# DRONE_ESP_SHIELD.net
KiCad netlist of a schematic drawn in EasyEDA
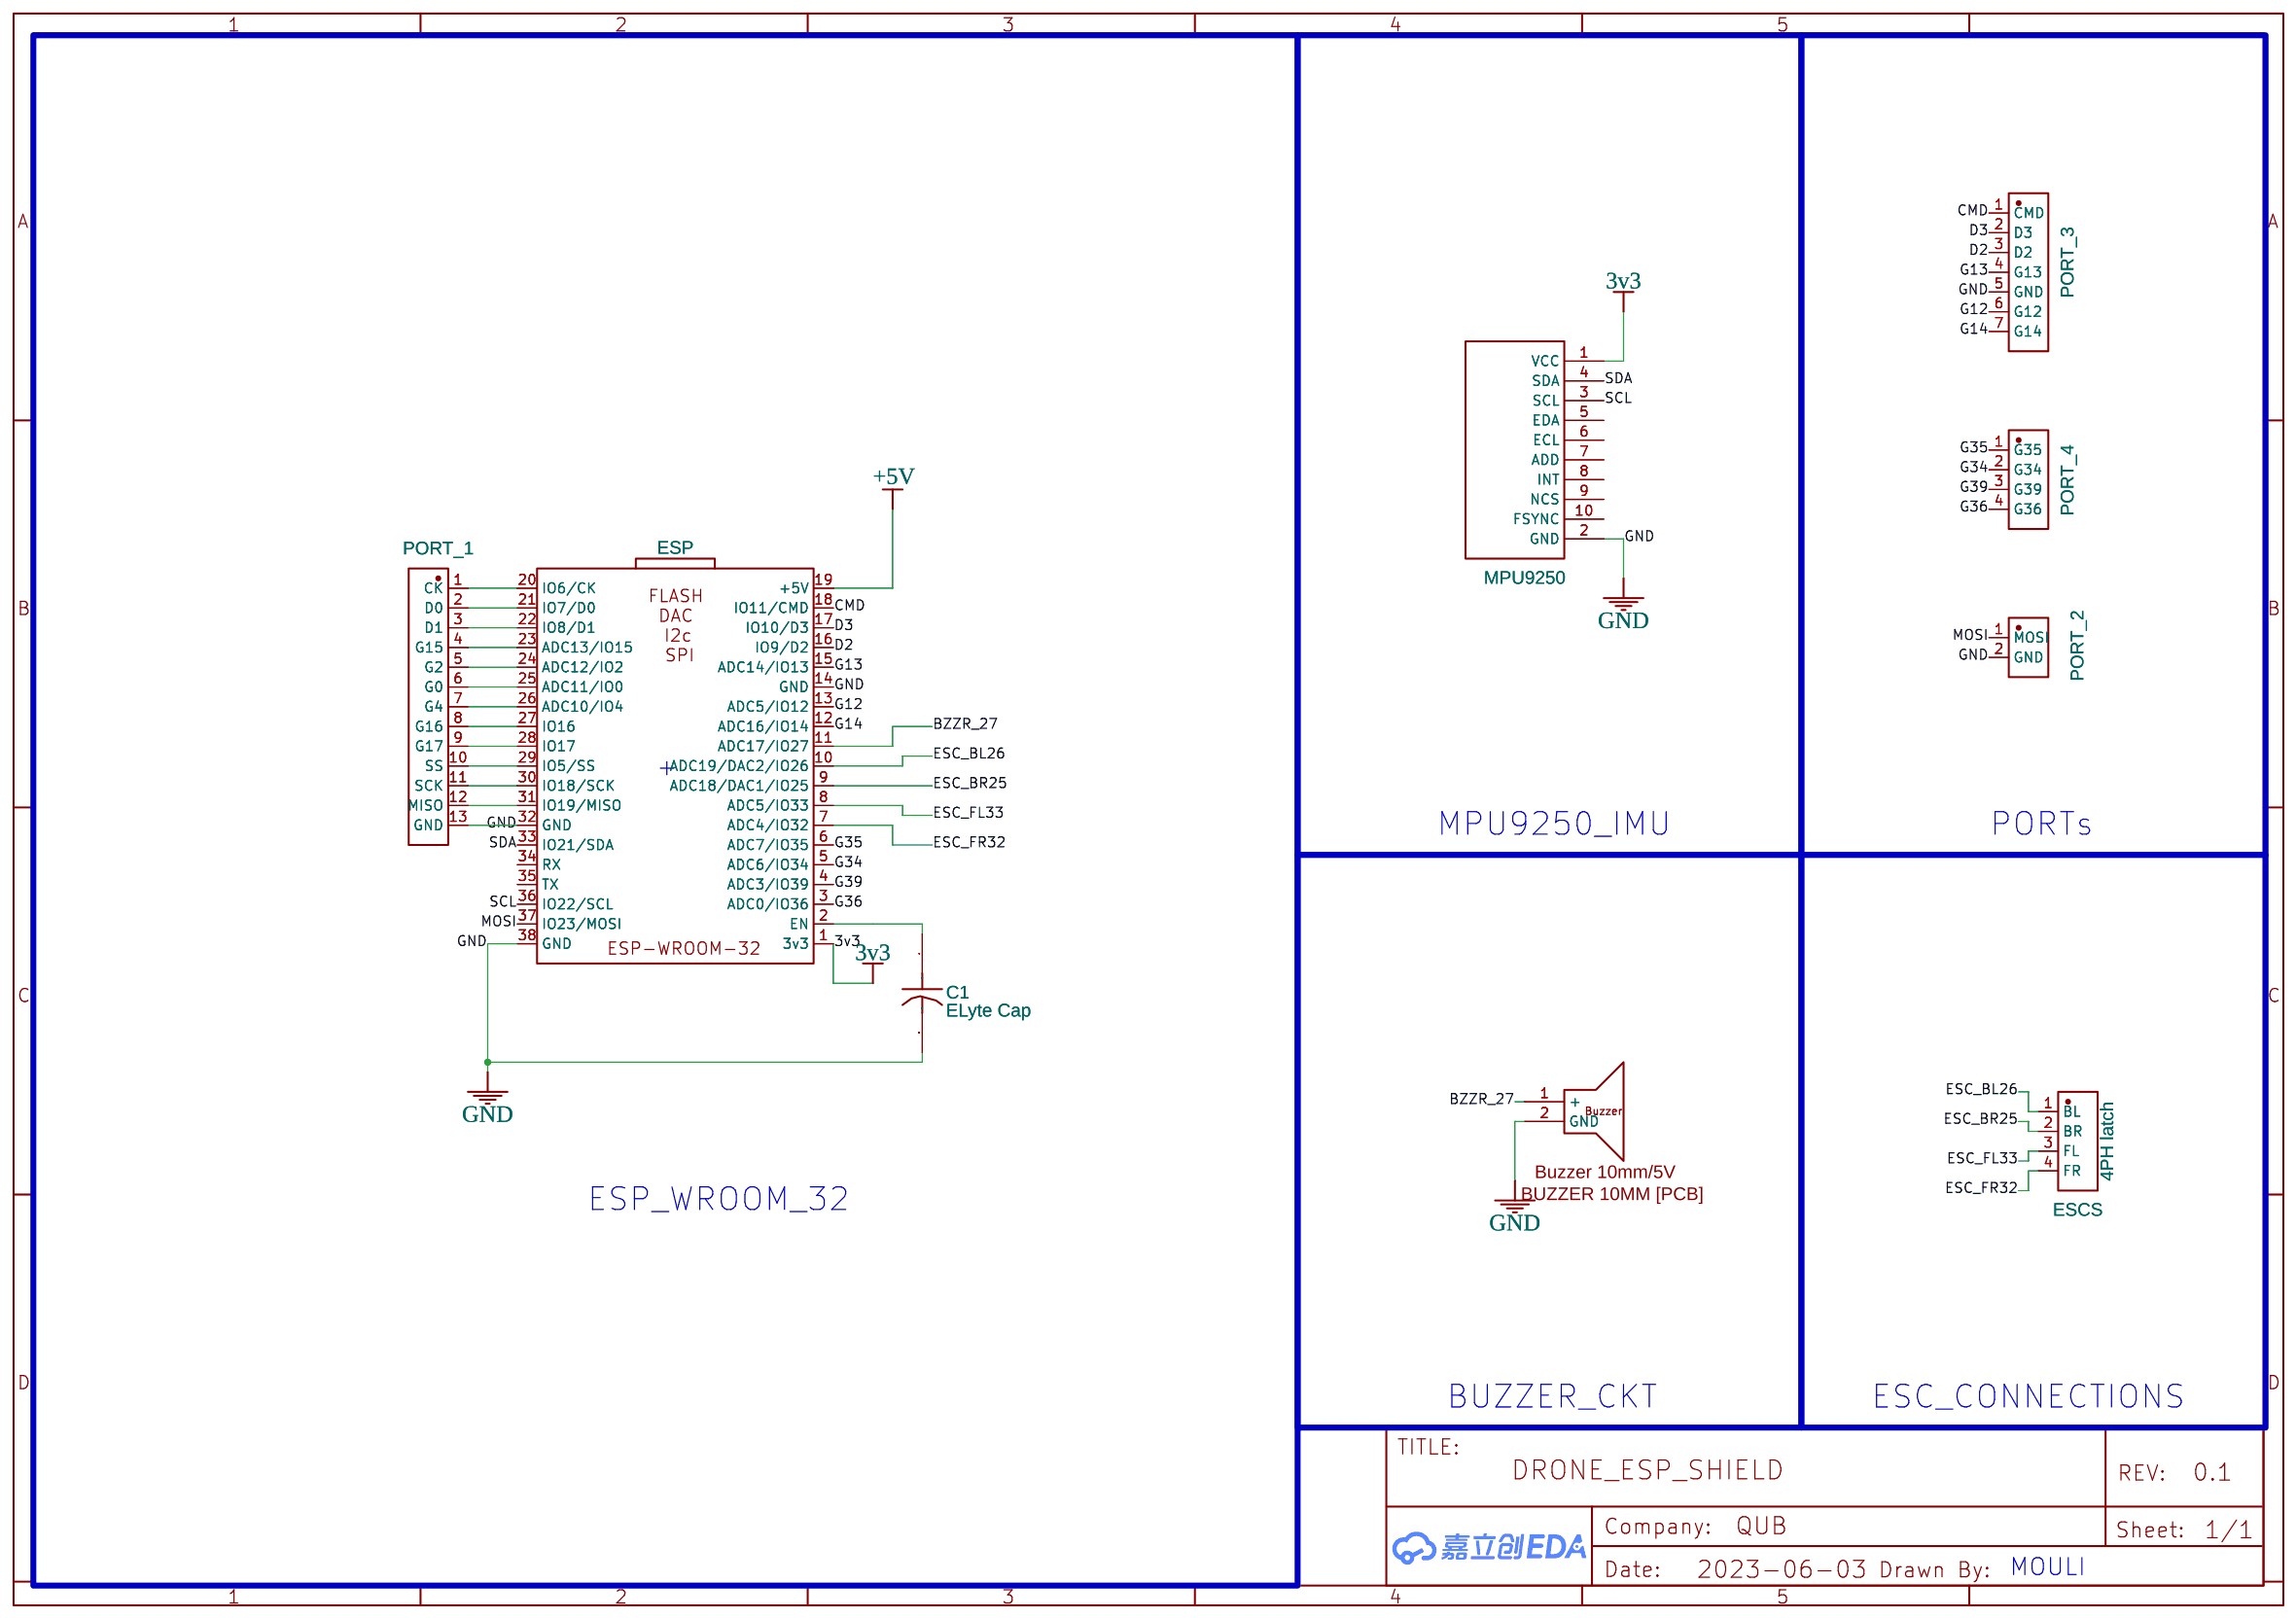
[diagram p0: schematic sheet]

(export (version "E")
  (design (tool "Eeschema 10.0.6"))
  (components
    (comp (ref "BUZZER")
      (value "Buzzer 10mm/5V")
      (fields (field (name "BOM_Manufacturer Part") "BUZZER"))
      (libsource (lib "") (part "Buzzer 10mm/5V"))
    )
    (comp (ref "C1") (value "ELyte Cap") (libsource (lib "") (part "Electrolitic Capacitor")))
    (comp (ref "ESCS")
      (value "4PH latch")
      (fields
        (field (name "BOM_Manufacturer Part") "A2541HWV-4P")
        (field (name "BOM_Supplier Part") "C5176037")
      )
      (libsource (lib "") (part "A2541HWV-4P_C5176037"))
    )
    (comp (ref "ESP")
      (value "ESP-WROOM-32D 38 Pins")
      (fields (field (name "BOM_Manufacturer Part") "ESP-WROOM-32"))
      (libsource (lib "") (part "ESP-WROOM-32D 38 Pins"))
    )
    (comp (ref "MPU9250") (value "MPU9250") (libsource (lib "") (part "MPU9250 MODULE")))
    (comp (ref "PORT_1")
      (value "EXT_PORT")
      (fields
        (field (name "BOM_Manufacturer Part") "PZ254-1-13-Z-8.5KK")
        (field (name "BOM_Supplier Part") "C3012215")
      )
      (libsource (lib "") (part "PZ254-1-13-Z-8.5KK"))
    )
    (comp (ref "PORT_2")
      (value "HDR102")
      (fields (field (name "BOM_Supplier Part") "C9900001420"))
      (libsource (lib "") (part "HDR102"))
    )
    (comp (ref "PORT_3")
      (value "PZ254-1-07-Z-C")
      (fields (field (name "BOM_Supplier Part") "C5156434"))
      (libsource (lib "") (part "PZ254-1-07-Z-C"))
    )
    (comp (ref "PORT_4")
      (value "0022285044")
      (fields (field (name "BOM_Supplier Part") "C9900016049"))
      (libsource (lib "") (part "0022285044"))
    )
  )
  (nets
    (net (code "1") (name "+5V") (class "Default")
      (node (ref "ESP") (pin "19") (pinfunction "+5V_19") (pintype "unspecified"))
    )
    (net (code "2") (name "/BZZR_27") (class "Default")
      (node (ref "BUZZER") (pin "1") (pinfunction "+_1") (pintype "unspecified"))
      (node (ref "ESP") (pin "11") (pinfunction "ADC17/IO27_11") (pintype "unspecified"))
    )
    (net (code "3") (name "/CMD") (class "Default")
      (node (ref "ESP") (pin "18") (pinfunction "IO11/CMD_18") (pintype "unspecified"))
      (node (ref "PORT_3") (pin "1") (pinfunction "CMD_1") (pintype "unspecified"))
    )
    (net (code "4") (name "/D2") (class "Default")
      (node (ref "ESP") (pin "16") (pinfunction "IO9/D2_16") (pintype "unspecified"))
      (node (ref "PORT_3") (pin "3") (pinfunction "D2_3") (pintype "unspecified"))
    )
    (net (code "5") (name "/D3") (class "Default")
      (node (ref "ESP") (pin "17") (pinfunction "IO10/D3_17") (pintype "unspecified"))
      (node (ref "PORT_3") (pin "2") (pinfunction "D3_2") (pintype "unspecified"))
    )
    (net (code "6") (name "/ESC_BL26") (class "Default")
      (node (ref "ESCS") (pin "1") (pinfunction "BL_1") (pintype "unspecified"))
      (node (ref "ESP") (pin "10") (pinfunction "ADC19/DAC2/IO26_10") (pintype "unspecified"))
    )
    (net (code "7") (name "/ESC_BR25") (class "Default")
      (node (ref "ESCS") (pin "2") (pinfunction "BR_2") (pintype "unspecified"))
      (node (ref "ESP") (pin "9") (pinfunction "ADC18/DAC1/IO25_9") (pintype "unspecified"))
    )
    (net (code "8") (name "/ESC_FL33") (class "Default")
      (node (ref "ESCS") (pin "3") (pinfunction "FL_3") (pintype "unspecified"))
      (node (ref "ESP") (pin "8") (pinfunction "ADC5/IO33_8") (pintype "unspecified"))
    )
    (net (code "9") (name "/ESC_FR32") (class "Default")
      (node (ref "ESCS") (pin "4") (pinfunction "FR_4") (pintype "unspecified"))
      (node (ref "ESP") (pin "7") (pinfunction "ADC4/IO32_7") (pintype "unspecified"))
    )
    (net (code "10") (name "/G12") (class "Default")
      (node (ref "ESP") (pin "13") (pinfunction "ADC5/IO12_13") (pintype "unspecified"))
      (node (ref "PORT_3") (pin "6") (pinfunction "G12_6") (pintype "unspecified"))
    )
    (net (code "11") (name "/G13") (class "Default")
      (node (ref "ESP") (pin "15") (pinfunction "ADC14/IO13_15") (pintype "unspecified"))
      (node (ref "PORT_3") (pin "4") (pinfunction "G13_4") (pintype "unspecified"))
    )
    (net (code "12") (name "/G14") (class "Default")
      (node (ref "ESP") (pin "12") (pinfunction "ADC16/IO14_12") (pintype "unspecified"))
      (node (ref "PORT_3") (pin "7") (pinfunction "G14_7") (pintype "unspecified"))
    )
    (net (code "13") (name "/G34") (class "Default")
      (node (ref "ESP") (pin "5") (pinfunction "ADC6/IO34_5") (pintype "unspecified"))
      (node (ref "PORT_4") (pin "2") (pinfunction "G34_2") (pintype "unspecified"))
    )
    (net (code "14") (name "/G35") (class "Default")
      (node (ref "ESP") (pin "6") (pinfunction "ADC7/IO35_6") (pintype "unspecified"))
      (node (ref "PORT_4") (pin "1") (pinfunction "G35_1") (pintype "unspecified"))
    )
    (net (code "15") (name "/G36") (class "Default")
      (node (ref "ESP") (pin "3") (pinfunction "ADC0/IO36_3") (pintype "unspecified"))
      (node (ref "PORT_4") (pin "4") (pinfunction "G36_4") (pintype "unspecified"))
    )
    (net (code "16") (name "/G39") (class "Default")
      (node (ref "ESP") (pin "4") (pinfunction "ADC3/IO39_4") (pintype "unspecified"))
      (node (ref "PORT_4") (pin "3") (pinfunction "G39_3") (pintype "unspecified"))
    )
    (net (code "17") (name "/MOSI") (class "Default")
      (node (ref "ESP") (pin "37") (pinfunction "IO23/MOSI_37") (pintype "unspecified"))
      (node (ref "PORT_2") (pin "1") (pinfunction "MOSI_1") (pintype "unspecified"))
    )
    (net (code "18") (name "/SCL") (class "Default")
      (node (ref "ESP") (pin "36") (pinfunction "IO22/SCL_36") (pintype "unspecified"))
      (node (ref "MPU9250") (pin "3") (pinfunction "SCL_3") (pintype "bidirectional"))
    )
    (net (code "19") (name "/SDA") (class "Default")
      (node (ref "ESP") (pin "33") (pinfunction "IO21/SDA_33") (pintype "unspecified"))
      (node (ref "MPU9250") (pin "4") (pinfunction "SDA_4") (pintype "bidirectional"))
    )
    (net (code "20") (name "3v3") (class "Default")
      (node (ref "ESP") (pin "1") (pinfunction "3v3_1") (pintype "unspecified"))
      (node (ref "MPU9250") (pin "1") (pinfunction "VCC_1") (pintype "passive"))
    )
    (net (code "21") (name "GND") (class "Default")
      (node (ref "BUZZER") (pin "2") (pinfunction "GND_2") (pintype "unspecified"))
      (node (ref "C1") (pin "2") (pinfunction "2_2") (pintype "unspecified"))
      (node (ref "ESP") (pin "14") (pinfunction "GND_14") (pintype "unspecified"))
      (node (ref "ESP") (pin "32") (pinfunction "GND_32") (pintype "unspecified"))
      (node (ref "ESP") (pin "38") (pinfunction "GND_38") (pintype "unspecified"))
      (node (ref "MPU9250") (pin "2") (pinfunction "GND_2") (pintype "passive"))
      (node (ref "PORT_1") (pin "13") (pinfunction "GND_13") (pintype "unspecified"))
      (node (ref "PORT_2") (pin "2") (pinfunction "GND_2") (pintype "unspecified"))
      (node (ref "PORT_3") (pin "5") (pinfunction "GND_5") (pintype "unspecified"))
    )
    (net (code "22") (name "Net-(ESP-ADC10{slash}IO4)") (class "Default")
      (node (ref "ESP") (pin "26") (pinfunction "ADC10/IO4_26") (pintype "unspecified"))
      (node (ref "PORT_1") (pin "7") (pinfunction "G4_7") (pintype "unspecified"))
    )
    (net (code "23") (name "Net-(ESP-ADC11{slash}IO0)") (class "Default")
      (node (ref "ESP") (pin "25") (pinfunction "ADC11/IO0_25") (pintype "unspecified"))
      (node (ref "PORT_1") (pin "6") (pinfunction "G0_6") (pintype "unspecified"))
    )
    (net (code "24") (name "Net-(ESP-ADC12{slash}IO2)") (class "Default")
      (node (ref "ESP") (pin "24") (pinfunction "ADC12/IO2_24") (pintype "unspecified"))
      (node (ref "PORT_1") (pin "5") (pinfunction "G2_5") (pintype "unspecified"))
    )
    (net (code "25") (name "Net-(ESP-ADC13{slash}IO15)") (class "Default")
      (node (ref "ESP") (pin "23") (pinfunction "ADC13/IO15_23") (pintype "unspecified"))
      (node (ref "PORT_1") (pin "4") (pinfunction "G15_4") (pintype "unspecified"))
    )
    (net (code "26") (name "Net-(ESP-EN)") (class "Default")
      (node (ref "C1") (pin "1") (pinfunction "1_1") (pintype "unspecified"))
      (node (ref "ESP") (pin "2") (pinfunction "EN_2") (pintype "unspecified"))
    )
    (net (code "27") (name "Net-(ESP-IO5{slash}SS)") (class "Default")
      (node (ref "ESP") (pin "29") (pinfunction "IO5/SS_29") (pintype "unspecified"))
      (node (ref "PORT_1") (pin "10") (pinfunction "SS_10") (pintype "unspecified"))
    )
    (net (code "28") (name "Net-(ESP-IO6{slash}CK)") (class "Default")
      (node (ref "ESP") (pin "20") (pinfunction "IO6/CK_20") (pintype "unspecified"))
      (node (ref "PORT_1") (pin "1") (pinfunction "CK_1") (pintype "unspecified"))
    )
    (net (code "29") (name "Net-(ESP-IO7{slash}D0)") (class "Default")
      (node (ref "ESP") (pin "21") (pinfunction "IO7/D0_21") (pintype "unspecified"))
      (node (ref "PORT_1") (pin "2") (pinfunction "D0_2") (pintype "unspecified"))
    )
    (net (code "30") (name "Net-(ESP-IO8{slash}D1)") (class "Default")
      (node (ref "ESP") (pin "22") (pinfunction "IO8/D1_22") (pintype "unspecified"))
      (node (ref "PORT_1") (pin "3") (pinfunction "D1_3") (pintype "unspecified"))
    )
    (net (code "31") (name "Net-(ESP-IO16)") (class "Default")
      (node (ref "ESP") (pin "27") (pinfunction "IO16_27") (pintype "unspecified"))
      (node (ref "PORT_1") (pin "8") (pinfunction "G16_8") (pintype "unspecified"))
    )
    (net (code "32") (name "Net-(ESP-IO17)") (class "Default")
      (node (ref "ESP") (pin "28") (pinfunction "IO17_28") (pintype "unspecified"))
      (node (ref "PORT_1") (pin "9") (pinfunction "G17_9") (pintype "unspecified"))
    )
    (net (code "33") (name "Net-(ESP-IO18{slash}SCK)") (class "Default")
      (node (ref "ESP") (pin "30") (pinfunction "IO18/SCK_30") (pintype "unspecified"))
      (node (ref "PORT_1") (pin "11") (pinfunction "SCK_11") (pintype "unspecified"))
    )
    (net (code "34") (name "Net-(ESP-IO19{slash}MISO)") (class "Default")
      (node (ref "ESP") (pin "31") (pinfunction "IO19/MISO_31") (pintype "unspecified"))
      (node (ref "PORT_1") (pin "12") (pinfunction "MISO_12") (pintype "unspecified"))
    )
    (net (code "35") (name "unconnected-(ESP-RX-Pad34)") (class "Default")
      (node (ref "ESP") (pin "34") (pinfunction "RX_34") (pintype "unspecified"))
    )
    (net (code "36") (name "unconnected-(ESP-TX-Pad35)") (class "Default")
      (node (ref "ESP") (pin "35") (pinfunction "TX_35") (pintype "unspecified"))
    )
    (net (code "37") (name "unconnected-(MPU9250-ADD-Pad7)") (class "Default")
      (node (ref "MPU9250") (pin "7") (pinfunction "ADD_7") (pintype "bidirectional"))
    )
    (net (code "38") (name "unconnected-(MPU9250-ECL-Pad6)") (class "Default")
      (node (ref "MPU9250") (pin "6") (pinfunction "ECL_6") (pintype "bidirectional"))
    )
    (net (code "39") (name "unconnected-(MPU9250-EDA-Pad5)") (class "Default")
      (node (ref "MPU9250") (pin "5") (pinfunction "EDA_5") (pintype "bidirectional"))
    )
    (net (code "40") (name "unconnected-(MPU9250-FSYNC-Pad10)") (class "Default")
      (node (ref "MPU9250") (pin "10") (pinfunction "FSYNC_10") (pintype "bidirectional"))
    )
    (net (code "41") (name "unconnected-(MPU9250-INT-Pad8)") (class "Default")
      (node (ref "MPU9250") (pin "8") (pinfunction "INT_8") (pintype "bidirectional"))
    )
    (net (code "42") (name "unconnected-(MPU9250-NCS-Pad9)") (class "Default")
      (node (ref "MPU9250") (pin "9") (pinfunction "NCS_9") (pintype "bidirectional"))
    )
  )
)
